# handheld_main.net
KiCad netlist of a schematic drawn in Altium Designer
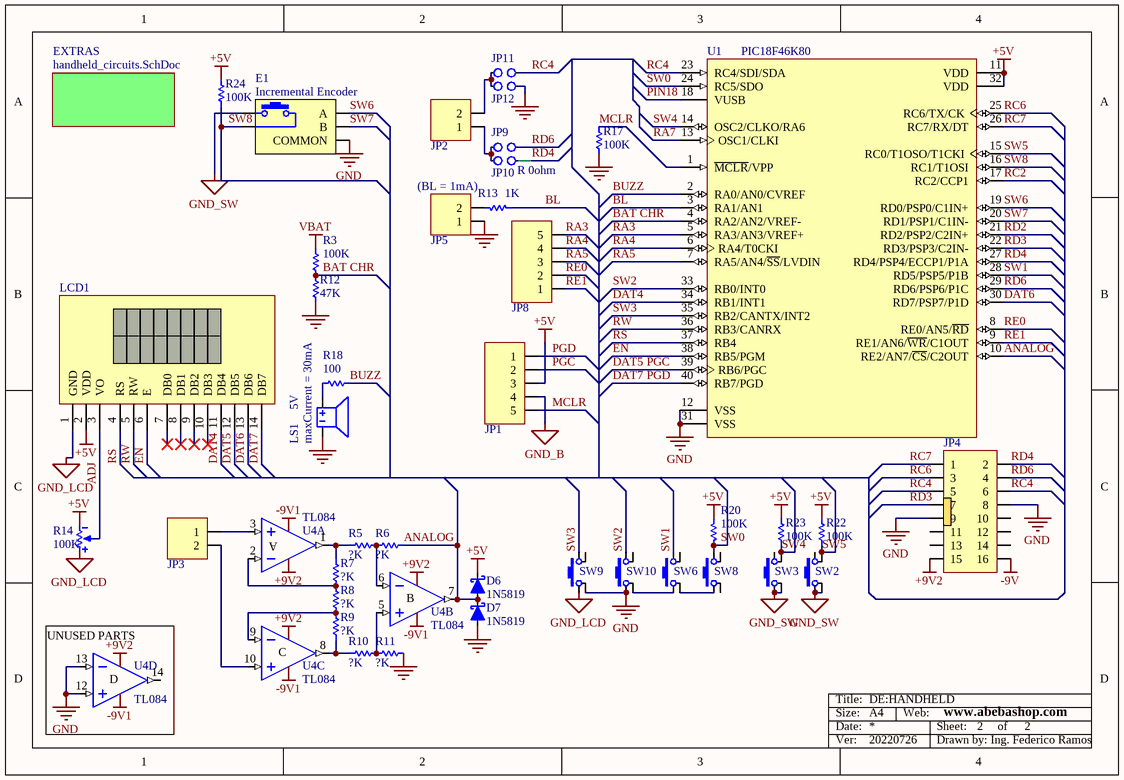
[diagram p0: handheld_main.SchDoc]

(export (version "E")
  (design (tool "Eeschema 10.0.6"))
  (components
    (comp (ref "D6")
      (value "1N5819")
      (footprint "d_do41")
      (description "Schottky Diode 1A 40V")
      (libsource (lib "FEDE") (part "1N5819"))
    )
    (comp (ref "D7")
      (value "1N5819")
      (footprint "d_do41")
      (description "Schottky Diode 1A 40V")
      (libsource (lib "FEDE") (part "1N5819"))
    )
    (comp (ref "E1")
      (value "Incremental Encoder")
      (footprint "encoder")
      (description "Incremental Encoder with Switch")
      (libsource (lib "FEDE") (part "Incremental Encoder"))
    )
    (comp (ref "JP1")
      (value "Header5x1")
      (footprint "HDR5x1")
      (description "Header 5x1")
      (libsource (lib "") (part "Header5x1_1"))
    )
    (comp (ref "JP2")
      (value "XY128V-A2P")
      (footprint "bornera2")
      (description "Bornera Tornillos 2x1; Altura = 13.8mm")
      (libsource (lib "") (part "Bornera Tornillos 2x1; Altura = 13.8mm_1"))
    )
    (comp (ref "JP3")
      (value "XY128V-A2P")
      (footprint "bornera2")
      (description "Bornera Tornillos 2x1; Altura = 13.8mm")
      (libsource (lib "FEDE") (part "Bornera Tornillos 2x1; Altura = 13.8mm"))
    )
    (comp (ref "JP4")
      (value "IDC 8x2 90deg")
      (footprint "idc8x2_90")
      (libsource (lib "FEDE") (part "IDC 8x2 90deg"))
    )
    (comp (ref "JP5")
      (value "Header2x1")
      (footprint "CONPOL2X1")
      (description "Header 2x1")
      (libsource (lib "FEDE") (part "Header2x1"))
    )
    (comp (ref "JP8")
      (value "Header5x1")
      (footprint "HDR5x1")
      (description "Header 5x1")
      (libsource (lib "FEDE") (part "Header5x1"))
    )
    (comp (ref "JP9")
      (value "Jumper 2 contactos; Soldadura")
      (footprint "JUMPER2")
      (libsource (lib "FEDE") (part "Jumper 2 contactos; Soldadura"))
    )
    (comp (ref "JP10")
      (value "Jumper 2 contactos; Soldadura")
      (footprint "JUMPER2")
      (libsource (lib "FEDE") (part "Jumper 2 contactos; Soldadura"))
    )
    (comp (ref "JP11")
      (value "Jumper 2 contactos; Soldadura")
      (footprint "JUMPER2")
      (libsource (lib "FEDE") (part "Jumper 2 contactos; Soldadura"))
    )
    (comp (ref "JP12")
      (value "Jumper 2 contactos; Soldadura")
      (footprint "JUMPER2")
      (libsource (lib "FEDE") (part "Jumper 2 contactos; Soldadura"))
    )
    (comp (ref "LCD1") (value "LCD 8X2") (footprint "LCD_0802") (libsource (lib "FEDE") (part "LCD 8X2")))
    (comp (ref "LS1")
      (value "5V")
      (footprint "ENC_SON_BUZ_12MM")
      (description "Buzzer")
      (fields (field (name "PRICE") "maxCurrent = 30mA"))
      (libsource (lib "FEDE") (part "Buzzer"))
    )
    (comp (ref "R3")
      (value "Resistencia 1206; 1Kohm")
      (footprint "R1206")
      (fields (field (name "RESISTENCIA") "100K"))
      (libsource (lib "FEDE") (part "Resistencia 1206; 1Kohm"))
    )
    (comp (ref "R5")
      (value "Resistencia 1206; 1Kohm")
      (footprint "RES300TH")
      (fields (field (name "RESISTENCIA") "?K"))
      (libsource (lib "FEDE") (part "Resistencia 1206; 1Kohm"))
    )
    (comp (ref "R6")
      (value "Resistencia 1206; 1Kohm")
      (footprint "RES300TH")
      (fields (field (name "RESISTENCIA") "?K"))
      (libsource (lib "FEDE") (part "Resistencia 1206; 1Kohm"))
    )
    (comp (ref "R7")
      (value "Resistencia 1206; 1Kohm")
      (footprint "RES300TH")
      (fields (field (name "RESISTENCIA") "?K"))
      (libsource (lib "FEDE") (part "Resistencia 1206; 1Kohm"))
    )
    (comp (ref "R8")
      (value "Resistencia 1206; 1Kohm")
      (footprint "RES300TH")
      (fields (field (name "RESISTENCIA") "?K"))
      (libsource (lib "FEDE") (part "Resistencia 1206; 1Kohm"))
    )
    (comp (ref "R9")
      (value "Resistencia 1206; 1Kohm")
      (footprint "RES300TH")
      (fields (field (name "RESISTENCIA") "?K"))
      (libsource (lib "FEDE") (part "Resistencia 1206; 1Kohm"))
    )
    (comp (ref "R10")
      (value "Resistencia 1206; 1Kohm")
      (footprint "RES300TH")
      (fields (field (name "RESISTENCIA") "?K"))
      (libsource (lib "FEDE") (part "Resistencia 1206; 1Kohm"))
    )
    (comp (ref "R11")
      (value "Resistencia 1206; 1Kohm")
      (footprint "RES300TH")
      (fields (field (name "RESISTENCIA") "?K"))
      (libsource (lib "FEDE") (part "Resistencia 1206; 1Kohm"))
    )
    (comp (ref "R12")
      (value "Resistencia 1206; 1Kohm")
      (footprint "R1206")
      (fields (field (name "RESISTENCIA") "47K"))
      (libsource (lib "FEDE") (part "Resistencia 1206; 1Kohm"))
    )
    (comp (ref "R13")
      (value "Resistencia 1206; 1Kohm")
      (footprint "R1206")
      (fields (field (name "CODIGO ELEMON") "(BL = 1mA)") (field (name "RESISTENCIA") "1K"))
      (libsource (lib "FEDE") (part "Resistencia 1206; 1Kohm"))
    )
    (comp (ref "R14")
      (value "100K")
      (footprint "PRESET6")
      (description "Resistencia Variable")
      (fields (field (name "Comment") "Preset"))
      (libsource (lib "FEDE") (part "Preset"))
    )
    (comp (ref "R17")
      (value "Resistencia 1206; 1Kohm")
      (footprint "RES300TH")
      (fields (field (name "RESISTENCIA") "100K"))
      (libsource (lib "FEDE") (part "Resistencia 1206; 1Kohm"))
    )
    (comp (ref "R18")
      (value "Resistencia 1206; 1Kohm")
      (footprint "R1206")
      (fields (field (name "RESISTENCIA") "100"))
      (libsource (lib "FEDE") (part "Resistencia 1206; 1Kohm"))
    )
    (comp (ref "R20")
      (value "Resistencia 1206; 1Kohm")
      (footprint "R1206")
      (fields (field (name "RESISTENCIA") "100K"))
      (libsource (lib "FEDE") (part "Resistencia 1206; 1Kohm"))
    )
    (comp (ref "R22")
      (value "Resistencia 1206; 1Kohm")
      (footprint "R1206")
      (fields (field (name "RESISTENCIA") "100K"))
      (libsource (lib "FEDE") (part "Resistencia 1206; 1Kohm"))
    )
    (comp (ref "R23")
      (value "Resistencia 1206; 1Kohm")
      (footprint "R1206")
      (fields (field (name "RESISTENCIA") "100K"))
      (libsource (lib "FEDE") (part "Resistencia 1206; 1Kohm"))
    )
    (comp (ref "R24")
      (value "Resistencia 1206; 1Kohm")
      (footprint "R1206")
      (fields (field (name "RESISTENCIA") "100K"))
      (libsource (lib "FEDE") (part "Resistencia 1206; 1Kohm"))
    )
    (comp (ref "R27")
      (value "R 0ohm")
      (footprint "R1206")
      (description "Resistencia 1206; 0ohm")
      (libsource (lib "FEDE") (part "Resistencia 1206; 0ohm"))
    )
    (comp (ref "SW2")
      (value "SW_T_17-5MM")
      (footprint "SW_T_17-5MM")
      (libsource (lib "FEDE") (part "SW_T_17-5MM"))
    )
    (comp (ref "SW3")
      (value "SW_T_17-5MM")
      (footprint "SW_T_17-5MM")
      (libsource (lib "FEDE") (part "SW_T_17-5MM"))
    )
    (comp (ref "SW6")
      (value "SW_T_17-5MM")
      (footprint "SW_T_17-5MM")
      (libsource (lib "FEDE") (part "SW_T_17-5MM"))
    )
    (comp (ref "SW8")
      (value "SW_T_17-5MM")
      (footprint "SW_T_17-5MM")
      (libsource (lib "FEDE") (part "SW_T_17-5MM"))
    )
    (comp (ref "SW9")
      (value "SW_T_17-5MM")
      (footprint "SW_T_17-5MM")
      (libsource (lib "FEDE") (part "SW_T_17-5MM"))
    )
    (comp (ref "SW10")
      (value "SW_T_17-5MM")
      (footprint "SW_T_17-5MM")
      (libsource (lib "FEDE") (part "SW_T_17-5MM"))
    )
    (comp (ref "U1")
      (value "PIC18F46K80")
      (footprint "DIP40Z_MICROCHIP")
      (description "FLASH Microcontroller")
      (libsource (lib "FEDE") (part "PIC18F4620"))
    )
    (comp (ref "U4")
      (value "TL084")
      (footprint "DIP14Z")
      (description "JFET-Input Operational Amplifier")
      (libsource (lib "FEDE") (part "TL084"))
    )
  )
  (nets
    (net (code "1") (name "+5V") (class "Default")
      (node (ref "D6") (pin "2") (pinfunction "K_2") (pintype "passive"))
      (node (ref "JP1") (pin "3") (pinfunction "3_3") (pintype "passive"))
      (node (ref "LCD1") (pin "2") (pinfunction "VDD_2") (pintype "passive"))
      (node (ref "R14") (pin "3") (pinfunction "3_3") (pintype "passive"))
      (node (ref "R20") (pin "1") (pinfunction "1_1") (pintype "passive"))
      (node (ref "R22") (pin "1") (pinfunction "1_1") (pintype "passive"))
      (node (ref "R23") (pin "1") (pinfunction "1_1") (pintype "passive"))
      (node (ref "R24") (pin "1") (pinfunction "1_1") (pintype "passive"))
      (node (ref "U1") (pin "11") (pinfunction "VDD_11") (pintype "power_in"))
      (node (ref "U1") (pin "32") (pinfunction "VDD_32") (pintype "power_in"))
    )
    (net (code "2") (name "+9V2") (class "Default")
      (node (ref "JP4") (pin "15") (pinfunction "15_15") (pintype "passive"))
      (node (ref "U4") (pin "4") (pinfunction "V+_4") (pintype "power_in"))
    )
    (net (code "3") (name "-9V") (class "Default")
      (node (ref "JP4") (pin "16") (pinfunction "16_16") (pintype "passive"))
    )
    (net (code "4") (name "-9V1") (class "Default")
      (node (ref "U4") (pin "11") (pinfunction "V-_11") (pintype "power_in"))
    )
    (net (code "5") (name "/ADJ") (class "Default")
      (node (ref "LCD1") (pin "3") (pinfunction "VO_3") (pintype "passive"))
      (node (ref "R14") (pin "2") (pinfunction "2_2") (pintype "passive"))
    )
    (net (code "6") (name "/ANALOG") (class "Default")
      (node (ref "D6") (pin "1") (pinfunction "A_1") (pintype "passive"))
      (node (ref "D7") (pin "2") (pinfunction "K_2") (pintype "passive"))
      (node (ref "R6") (pin "2") (pinfunction "2_2") (pintype "passive"))
      (node (ref "U1") (pin "10") (pinfunction "RE2/AN7/~{CS}/C2OUT_10") (pintype "bidirectional"))
      (node (ref "U4") (pin "7") (pinfunction "OUT_7") (pintype "output"))
    )
    (net (code "7") (name "/BAT CHR") (class "Default")
      (node (ref "R12") (pin "1") (pinfunction "1_1") (pintype "passive"))
      (node (ref "R3") (pin "2") (pinfunction "2_2") (pintype "passive"))
      (node (ref "U1") (pin "4") (pinfunction "RA2/AN2/VREF-_4") (pintype "bidirectional"))
    )
    (net (code "8") (name "/BL") (class "Default")
      (node (ref "R13") (pin "1") (pinfunction "1_1") (pintype "passive"))
      (node (ref "U1") (pin "3") (pinfunction "RA1/AN1_3") (pintype "bidirectional"))
    )
    (net (code "9") (name "/BUZZ") (class "Default")
      (node (ref "R18") (pin "2") (pinfunction "2_2") (pintype "passive"))
      (node (ref "U1") (pin "2") (pinfunction "RA0/AN0/CVREF_2") (pintype "bidirectional"))
    )
    (net (code "10") (name "/DAT4") (class "Default")
      (node (ref "LCD1") (pin "11") (pinfunction "DB4_11") (pintype "passive"))
      (node (ref "U1") (pin "34") (pinfunction "RB1/INT1_34") (pintype "bidirectional"))
    )
    (net (code "11") (name "/DAT5") (class "Default")
      (node (ref "JP1") (pin "2") (pinfunction "2_2") (pintype "passive"))
      (node (ref "LCD1") (pin "12") (pinfunction "DB5_12") (pintype "passive"))
      (node (ref "U1") (pin "39") (pinfunction "RB6/PGC_39") (pintype "bidirectional"))
    )
    (net (code "12") (name "/DAT6") (class "Default")
      (node (ref "LCD1") (pin "13") (pinfunction "DB6_13") (pintype "passive"))
      (node (ref "U1") (pin "30") (pinfunction "RD7/PSP7/P1D_30") (pintype "bidirectional"))
    )
    (net (code "13") (name "/DAT7") (class "Default")
      (node (ref "JP1") (pin "1") (pinfunction "1_1") (pintype "passive"))
      (node (ref "LCD1") (pin "14") (pinfunction "DB7_14") (pintype "passive"))
      (node (ref "U1") (pin "40") (pinfunction "RB7/PGD_40") (pintype "bidirectional"))
    )
    (net (code "14") (name "/EN") (class "Default")
      (node (ref "LCD1") (pin "6") (pinfunction "E_6") (pintype "passive"))
      (node (ref "U1") (pin "38") (pinfunction "RB5/PGM_38") (pintype "bidirectional"))
    )
    (net (code "15") (name "/MCLR") (class "Default")
      (node (ref "JP1") (pin "5") (pinfunction "5_5") (pintype "passive"))
      (node (ref "R17") (pin "1") (pinfunction "1_1") (pintype "passive"))
      (node (ref "U1") (pin "1") (pinfunction "~{MCLR}/VPP_1") (pintype "input"))
    )
    (net (code "16") (name "/PIN18") (class "Default")
      (node (ref "U1") (pin "18") (pinfunction "VUSB_18") (pintype "power_in"))
    )
    (net (code "17") (name "/RA3") (class "Default")
      (node (ref "JP8") (pin "5") (pinfunction "5_5") (pintype "passive"))
      (node (ref "U1") (pin "5") (pinfunction "RA3/AN3/VREF+_5") (pintype "bidirectional"))
    )
    (net (code "18") (name "/RA4") (class "Default")
      (node (ref "JP8") (pin "4") (pinfunction "4_4") (pintype "passive"))
      (node (ref "U1") (pin "6") (pinfunction "RA4/T0CKI_6") (pintype "bidirectional"))
    )
    (net (code "19") (name "/RA5") (class "Default")
      (node (ref "JP8") (pin "3") (pinfunction "3_3") (pintype "passive"))
      (node (ref "U1") (pin "7") (pinfunction "RA5/AN4/~{SS}/LVDIN_7") (pintype "bidirectional"))
    )
    (net (code "20") (name "/RA7") (class "Default")
      (node (ref "U1") (pin "13") (pinfunction "OSC1/CLKI_13") (pintype "input"))
    )
    (net (code "21") (name "/RC2") (class "Default")
      (node (ref "U1") (pin "17") (pinfunction "RC2/CCP1_17") (pintype "bidirectional"))
    )
    (net (code "22") (name "/RC4") (class "Default")
      (node (ref "JP11") (pin "2") (pinfunction "2_2") (pintype "passive"))
      (node (ref "JP4") (pin "5") (pinfunction "5_5") (pintype "passive"))
      (node (ref "JP4") (pin "6") (pinfunction "6_6") (pintype "passive"))
      (node (ref "U1") (pin "23") (pinfunction "RC4/SDI/SDA_23") (pintype "input"))
    )
    (net (code "23") (name "/RC6") (class "Default")
      (node (ref "JP4") (pin "3") (pinfunction "3_3") (pintype "passive"))
      (node (ref "U1") (pin "25") (pinfunction "RC6/TX/CK_25") (pintype "bidirectional"))
    )
    (net (code "24") (name "/RC7") (class "Default")
      (node (ref "JP4") (pin "1") (pinfunction "1_1") (pintype "passive"))
      (node (ref "U1") (pin "26") (pinfunction "RC7/RX/DT_26") (pintype "bidirectional"))
    )
    (net (code "25") (name "/RD2") (class "Default")
      (node (ref "U1") (pin "21") (pinfunction "RD2/PSP2/C2IN+_21") (pintype "bidirectional"))
    )
    (net (code "26") (name "/RD3") (class "Default")
      (node (ref "JP4") (pin "7") (pinfunction "7_7") (pintype "passive"))
      (node (ref "U1") (pin "22") (pinfunction "RD3/PSP3/C2IN-_22") (pintype "bidirectional"))
    )
    (net (code "27") (name "/RD4") (class "Default")
      (node (ref "JP4") (pin "2") (pinfunction "2_2") (pintype "passive"))
      (node (ref "R27") (pin "1") (pinfunction "1_1") (pintype "passive"))
      (node (ref "U1") (pin "27") (pinfunction "RD4/PSP4/ECCP1/P1A_27") (pintype "bidirectional"))
    )
    (net (code "28") (name "/RD6") (class "Default")
      (node (ref "JP4") (pin "4") (pinfunction "4_4") (pintype "passive"))
      (node (ref "JP9") (pin "2") (pinfunction "2_2") (pintype "passive"))
      (node (ref "U1") (pin "29") (pinfunction "RD6/PSP6/P1C_29") (pintype "bidirectional"))
    )
    (net (code "29") (name "/RE0") (class "Default")
      (node (ref "JP8") (pin "2") (pinfunction "2_2") (pintype "passive"))
      (node (ref "U1") (pin "8") (pinfunction "RE0/AN5/~{RD}_8") (pintype "bidirectional"))
    )
    (net (code "30") (name "/RE1") (class "Default")
      (node (ref "JP8") (pin "1") (pinfunction "1_1") (pintype "passive"))
      (node (ref "U1") (pin "9") (pinfunction "RE1/AN6/~{WR}/C1OUT_9") (pintype "bidirectional"))
    )
    (net (code "31") (name "/RS") (class "Default")
      (node (ref "LCD1") (pin "4") (pinfunction "RS_4") (pintype "passive"))
      (node (ref "U1") (pin "37") (pinfunction "RB4_37") (pintype "bidirectional"))
    )
    (net (code "32") (name "/RW") (class "Default")
      (node (ref "LCD1") (pin "5") (pinfunction "RW_5") (pintype "passive"))
      (node (ref "U1") (pin "36") (pinfunction "RB3/CANRX_36") (pintype "bidirectional"))
    )
    (net (code "33") (name "/SW0") (class "Default")
      (node (ref "R20") (pin "2") (pinfunction "2_2") (pintype "passive"))
      (node (ref "SW8") (pin "3") (pinfunction "3_3") (pintype "passive"))
      (node (ref "U1") (pin "24") (pinfunction "RC5/SDO_24") (pintype "input"))
    )
    (net (code "34") (name "/SW1") (class "Default")
      (node (ref "SW6") (pin "3") (pinfunction "3_3") (pintype "passive"))
      (node (ref "U1") (pin "28") (pinfunction "RD5/PSP5/P1B_28") (pintype "bidirectional"))
    )
    (net (code "35") (name "/SW2") (class "Default")
      (node (ref "SW10") (pin "3") (pinfunction "3_3") (pintype "passive"))
      (node (ref "U1") (pin "33") (pinfunction "RB0/INT0_33") (pintype "bidirectional"))
    )
    (net (code "36") (name "/SW3") (class "Default")
      (node (ref "SW9") (pin "3") (pinfunction "3_3") (pintype "passive"))
      (node (ref "U1") (pin "35") (pinfunction "RB2/CANTX/INT2_35") (pintype "bidirectional"))
    )
    (net (code "37") (name "/SW4") (class "Default")
      (node (ref "R23") (pin "2") (pinfunction "2_2") (pintype "passive"))
      (node (ref "SW3") (pin "1") (pinfunction "1_1") (pintype "passive"))
      (node (ref "U1") (pin "14") (pinfunction "OSC2/CLKO/RA6_14") (pintype "bidirectional"))
    )
    (net (code "38") (name "/SW5") (class "Default")
      (node (ref "R22") (pin "2") (pinfunction "2_2") (pintype "passive"))
      (node (ref "SW2") (pin "1") (pinfunction "1_1") (pintype "passive"))
      (node (ref "U1") (pin "15") (pinfunction "RC0/T1OSO/T1CKI_15") (pintype "bidirectional"))
    )
    (net (code "39") (name "/SW6") (class "Default")
      (node (ref "E1") (pin "1") (pinfunction "A_1") (pintype "passive"))
      (node (ref "U1") (pin "19") (pinfunction "RD0/PSP0/C1IN+_19") (pintype "bidirectional"))
    )
    (net (code "40") (name "/SW7") (class "Default")
      (node (ref "E1") (pin "3") (pinfunction "B_3") (pintype "passive"))
      (node (ref "U1") (pin "20") (pinfunction "RD1/PSP1/C1IN-_20") (pintype "bidirectional"))
    )
    (net (code "41") (name "/SW8") (class "Default")
      (node (ref "E1") (pin "5") (pintype "passive"))
      (node (ref "R24") (pin "2") (pinfunction "2_2") (pintype "passive"))
      (node (ref "U1") (pin "16") (pinfunction "RC1/T1OSI_16") (pintype "bidirectional"))
    )
    (net (code "42") (name "GND") (class "Default")
      (node (ref "D7") (pin "1") (pinfunction "A_1") (pintype "passive"))
      (node (ref "E1") (pin "2") (pinfunction "COMMON_2") (pintype "passive"))
      (node (ref "JP12") (pin "2") (pinfunction "2_2") (pintype "passive"))
      (node (ref "JP4") (pin "8") (pinfunction "8_8") (pintype "passive"))
      (node (ref "JP4") (pin "9") (pinfunction "9_9") (pintype "passive"))
      (node (ref "JP5") (pin "1") (pinfunction "1_1") (pintype "passive"))
      (node (ref "LS1") (pin "2") (pinfunction "2_2") (pintype "passive"))
      (node (ref "R11") (pin "2") (pinfunction "2_2") (pintype "passive"))
      (node (ref "R12") (pin "2") (pinfunction "2_2") (pintype "passive"))
      (node (ref "R17") (pin "2") (pinfunction "2_2") (pintype "passive"))
      (node (ref "SW10") (pin "4") (pinfunction "4_4") (pintype "passive"))
      (node (ref "SW9") (pin "2") (pinfunction "2_2") (pintype "passive"))
      (node (ref "U1") (pin "12") (pinfunction "VSS_12") (pintype "power_in"))
      (node (ref "U1") (pin "31") (pinfunction "VSS_31") (pintype "power_in"))
      (node (ref "U4") (pin "12") (pinfunction "IN+_12") (pintype "input"))
      (node (ref "U4") (pin "13") (pinfunction "IN-_13") (pintype "input"))
    )
    (net (code "43") (name "GND_B") (class "Default")
      (node (ref "JP1") (pin "4") (pinfunction "4_4") (pintype "passive"))
    )
    (net (code "44") (name "GND_LCD") (class "Default")
      (node (ref "LCD1") (pin "1") (pinfunction "GND_1") (pintype "passive"))
      (node (ref "R14") (pin "1") (pinfunction "1_1") (pintype "passive"))
      (node (ref "SW9") (pin "4") (pinfunction "4_4") (pintype "passive"))
    )
    (net (code "45") (name "GND_SW") (class "Default")
      (node (ref "E1") (pin "4") (pintype "passive"))
      (node (ref "SW2") (pin "2") (pinfunction "2_2") (pintype "passive"))
      (node (ref "SW2") (pin "4") (pinfunction "4_4") (pintype "passive"))
      (node (ref "SW3") (pin "2") (pinfunction "2_2") (pintype "passive"))
      (node (ref "SW3") (pin "4") (pinfunction "4_4") (pintype "passive"))
    )
    (net (code "46") (name "Net-(JP5-Pad2)") (class "Default")
      (node (ref "JP5") (pin "2") (pinfunction "2_2") (pintype "passive"))
      (node (ref "R13") (pin "2") (pinfunction "2_2") (pintype "passive"))
    )
    (net (code "47") (name "Net-(JP10-Pad1)") (class "Default")
      (node (ref "JP10") (pin "1") (pinfunction "1_1") (pintype "passive"))
      (node (ref "JP2") (pin "1") (pinfunction "1_1") (pintype "passive"))
      (node (ref "JP9") (pin "1") (pinfunction "1_1") (pintype "passive"))
    )
    (net (code "48") (name "Net-(JP10-Pad2)") (class "Default")
      (node (ref "JP10") (pin "2") (pinfunction "2_2") (pintype "passive"))
      (node (ref "R27") (pin "2") (pinfunction "2_2") (pintype "passive"))
    )
    (net (code "49") (name "Net-(JP11-Pad1)") (class "Default")
      (node (ref "JP11") (pin "1") (pinfunction "1_1") (pintype "passive"))
      (node (ref "JP12") (pin "1") (pinfunction "1_1") (pintype "passive"))
      (node (ref "JP2") (pin "2") (pinfunction "2_2") (pintype "passive"))
    )
    (net (code "50") (name "Net-(LS1-Pad1)") (class "Default")
      (node (ref "LS1") (pin "1") (pinfunction "1_1") (pintype "passive"))
      (node (ref "R18") (pin "1") (pinfunction "1_1") (pintype "passive"))
    )
    (net (code "51") (name "Net-(SW6-Pad2)") (class "Default")
      (node (ref "SW6") (pin "2") (pinfunction "2_2") (pintype "passive"))
      (node (ref "SW8") (pin "4") (pinfunction "4_4") (pintype "passive"))
    )
    (net (code "52") (name "Net-(SW10-Pad2)") (class "Default")
      (node (ref "SW10") (pin "2") (pinfunction "2_2") (pintype "passive"))
      (node (ref "SW6") (pin "4") (pinfunction "4_4") (pintype "passive"))
    )
    (net (code "53") (name "Net-(U4A-IN+)") (class "Default")
      (node (ref "JP3") (pin "1") (pinfunction "1_1") (pintype "passive"))
      (node (ref "U4") (pin "3") (pinfunction "IN+_3") (pintype "input"))
    )
    (net (code "54") (name "Net-(U4A-IN-)") (class "Default")
      (node (ref "R7") (pin "2") (pinfunction "2_2") (pintype "passive"))
      (node (ref "R8") (pin "1") (pinfunction "1_1") (pintype "passive"))
      (node (ref "U4") (pin "2") (pinfunction "IN-_2") (pintype "input"))
    )
    (net (code "55") (name "Net-(U4A-OUT)") (class "Default")
      (node (ref "R5") (pin "1") (pinfunction "1_1") (pintype "passive"))
      (node (ref "R7") (pin "1") (pinfunction "1_1") (pintype "passive"))
      (node (ref "U4") (pin "1") (pinfunction "OUT_1") (pintype "output"))
    )
    (net (code "56") (name "Net-(U4B-IN+)") (class "Default")
      (node (ref "R10") (pin "2") (pinfunction "2_2") (pintype "passive"))
      (node (ref "R11") (pin "1") (pinfunction "1_1") (pintype "passive"))
      (node (ref "U4") (pin "5") (pinfunction "IN+_5") (pintype "input"))
    )
    (net (code "57") (name "Net-(U4B-IN-)") (class "Default")
      (node (ref "R5") (pin "2") (pinfunction "2_2") (pintype "passive"))
      (node (ref "R6") (pin "1") (pinfunction "1_1") (pintype "passive"))
      (node (ref "U4") (pin "6") (pinfunction "IN-_6") (pintype "input"))
    )
    (net (code "58") (name "Net-(U4C-IN+)") (class "Default")
      (node (ref "JP3") (pin "2") (pinfunction "2_2") (pintype "passive"))
      (node (ref "U4") (pin "10") (pinfunction "IN+_10") (pintype "input"))
    )
    (net (code "59") (name "Net-(U4C-IN-)") (class "Default")
      (node (ref "R8") (pin "2") (pinfunction "2_2") (pintype "passive"))
      (node (ref "R9") (pin "1") (pinfunction "1_1") (pintype "passive"))
      (node (ref "U4") (pin "9") (pinfunction "IN-_9") (pintype "input"))
    )
    (net (code "60") (name "Net-(U4C-OUT)") (class "Default")
      (node (ref "R10") (pin "1") (pinfunction "1_1") (pintype "passive"))
      (node (ref "R9") (pin "2") (pinfunction "2_2") (pintype "passive"))
      (node (ref "U4") (pin "8") (pinfunction "OUT_8") (pintype "output"))
    )
    (net (code "61") (name "VBAT") (class "Default")
      (node (ref "R3") (pin "1") (pinfunction "1_1") (pintype "passive"))
    )
    (net (code "62") (name "unconnected-(JP4-Pad10)") (class "Default")
      (node (ref "JP4") (pin "10") (pinfunction "10_10") (pintype "passive"))
    )
    (net (code "63") (name "unconnected-(JP4-Pad11)") (class "Default")
      (node (ref "JP4") (pin "11") (pinfunction "11_11") (pintype "passive"))
    )
    (net (code "64") (name "unconnected-(JP4-Pad12)") (class "Default")
      (node (ref "JP4") (pin "12") (pinfunction "12_12") (pintype "passive"))
    )
    (net (code "65") (name "unconnected-(JP4-Pad13)") (class "Default")
      (node (ref "JP4") (pin "13") (pinfunction "13_13") (pintype "passive"))
    )
    (net (code "66") (name "unconnected-(JP4-Pad14)") (class "Default")
      (node (ref "JP4") (pin "14") (pinfunction "14_14") (pintype "passive"))
    )
    (net (code "67") (name "unconnected-(LCD1-DB0-Pad7)") (class "Default")
      (node (ref "LCD1") (pin "7") (pinfunction "DB0_7") (pintype "passive+no_connect"))
    )
    (net (code "68") (name "unconnected-(LCD1-DB1-Pad8)") (class "Default")
      (node (ref "LCD1") (pin "8") (pinfunction "DB1_8") (pintype "passive+no_connect"))
    )
    (net (code "69") (name "unconnected-(LCD1-DB2-Pad9)") (class "Default")
      (node (ref "LCD1") (pin "9") (pinfunction "DB2_9") (pintype "passive+no_connect"))
    )
    (net (code "70") (name "unconnected-(LCD1-DB3-Pad10)") (class "Default")
      (node (ref "LCD1") (pin "10") (pinfunction "DB3_10") (pintype "passive+no_connect"))
    )
    (net (code "71") (name "unconnected-(SW2-Pad3)") (class "Default")
      (node (ref "SW2") (pin "3") (pinfunction "3_3") (pintype "passive"))
    )
    (net (code "72") (name "unconnected-(SW3-Pad3)") (class "Default")
      (node (ref "SW3") (pin "3") (pinfunction "3_3") (pintype "passive"))
    )
    (net (code "73") (name "unconnected-(SW6-Pad1)") (class "Default")
      (node (ref "SW6") (pin "1") (pinfunction "1_1") (pintype "passive"))
    )
    (net (code "74") (name "unconnected-(SW8-Pad1)") (class "Default")
      (node (ref "SW8") (pin "1") (pinfunction "1_1") (pintype "passive"))
    )
    (net (code "75") (name "unconnected-(SW8-Pad2)") (class "Default")
      (node (ref "SW8") (pin "2") (pinfunction "2_2") (pintype "passive"))
    )
    (net (code "76") (name "unconnected-(SW9-Pad1)") (class "Default")
      (node (ref "SW9") (pin "1") (pinfunction "1_1") (pintype "passive"))
    )
    (net (code "77") (name "unconnected-(SW10-Pad1)") (class "Default")
      (node (ref "SW10") (pin "1") (pinfunction "1_1") (pintype "passive"))
    )
    (net (code "78") (name "unconnected-(U4D-OUT-Pad14)") (class "Default")
      (node (ref "U4") (pin "14") (pinfunction "OUT_14") (pintype "output"))
    )
  )
)
